# SCH_RETOFISH-V1_2025-09-10.net
KiCad netlist of a schematic drawn in EasyEDA
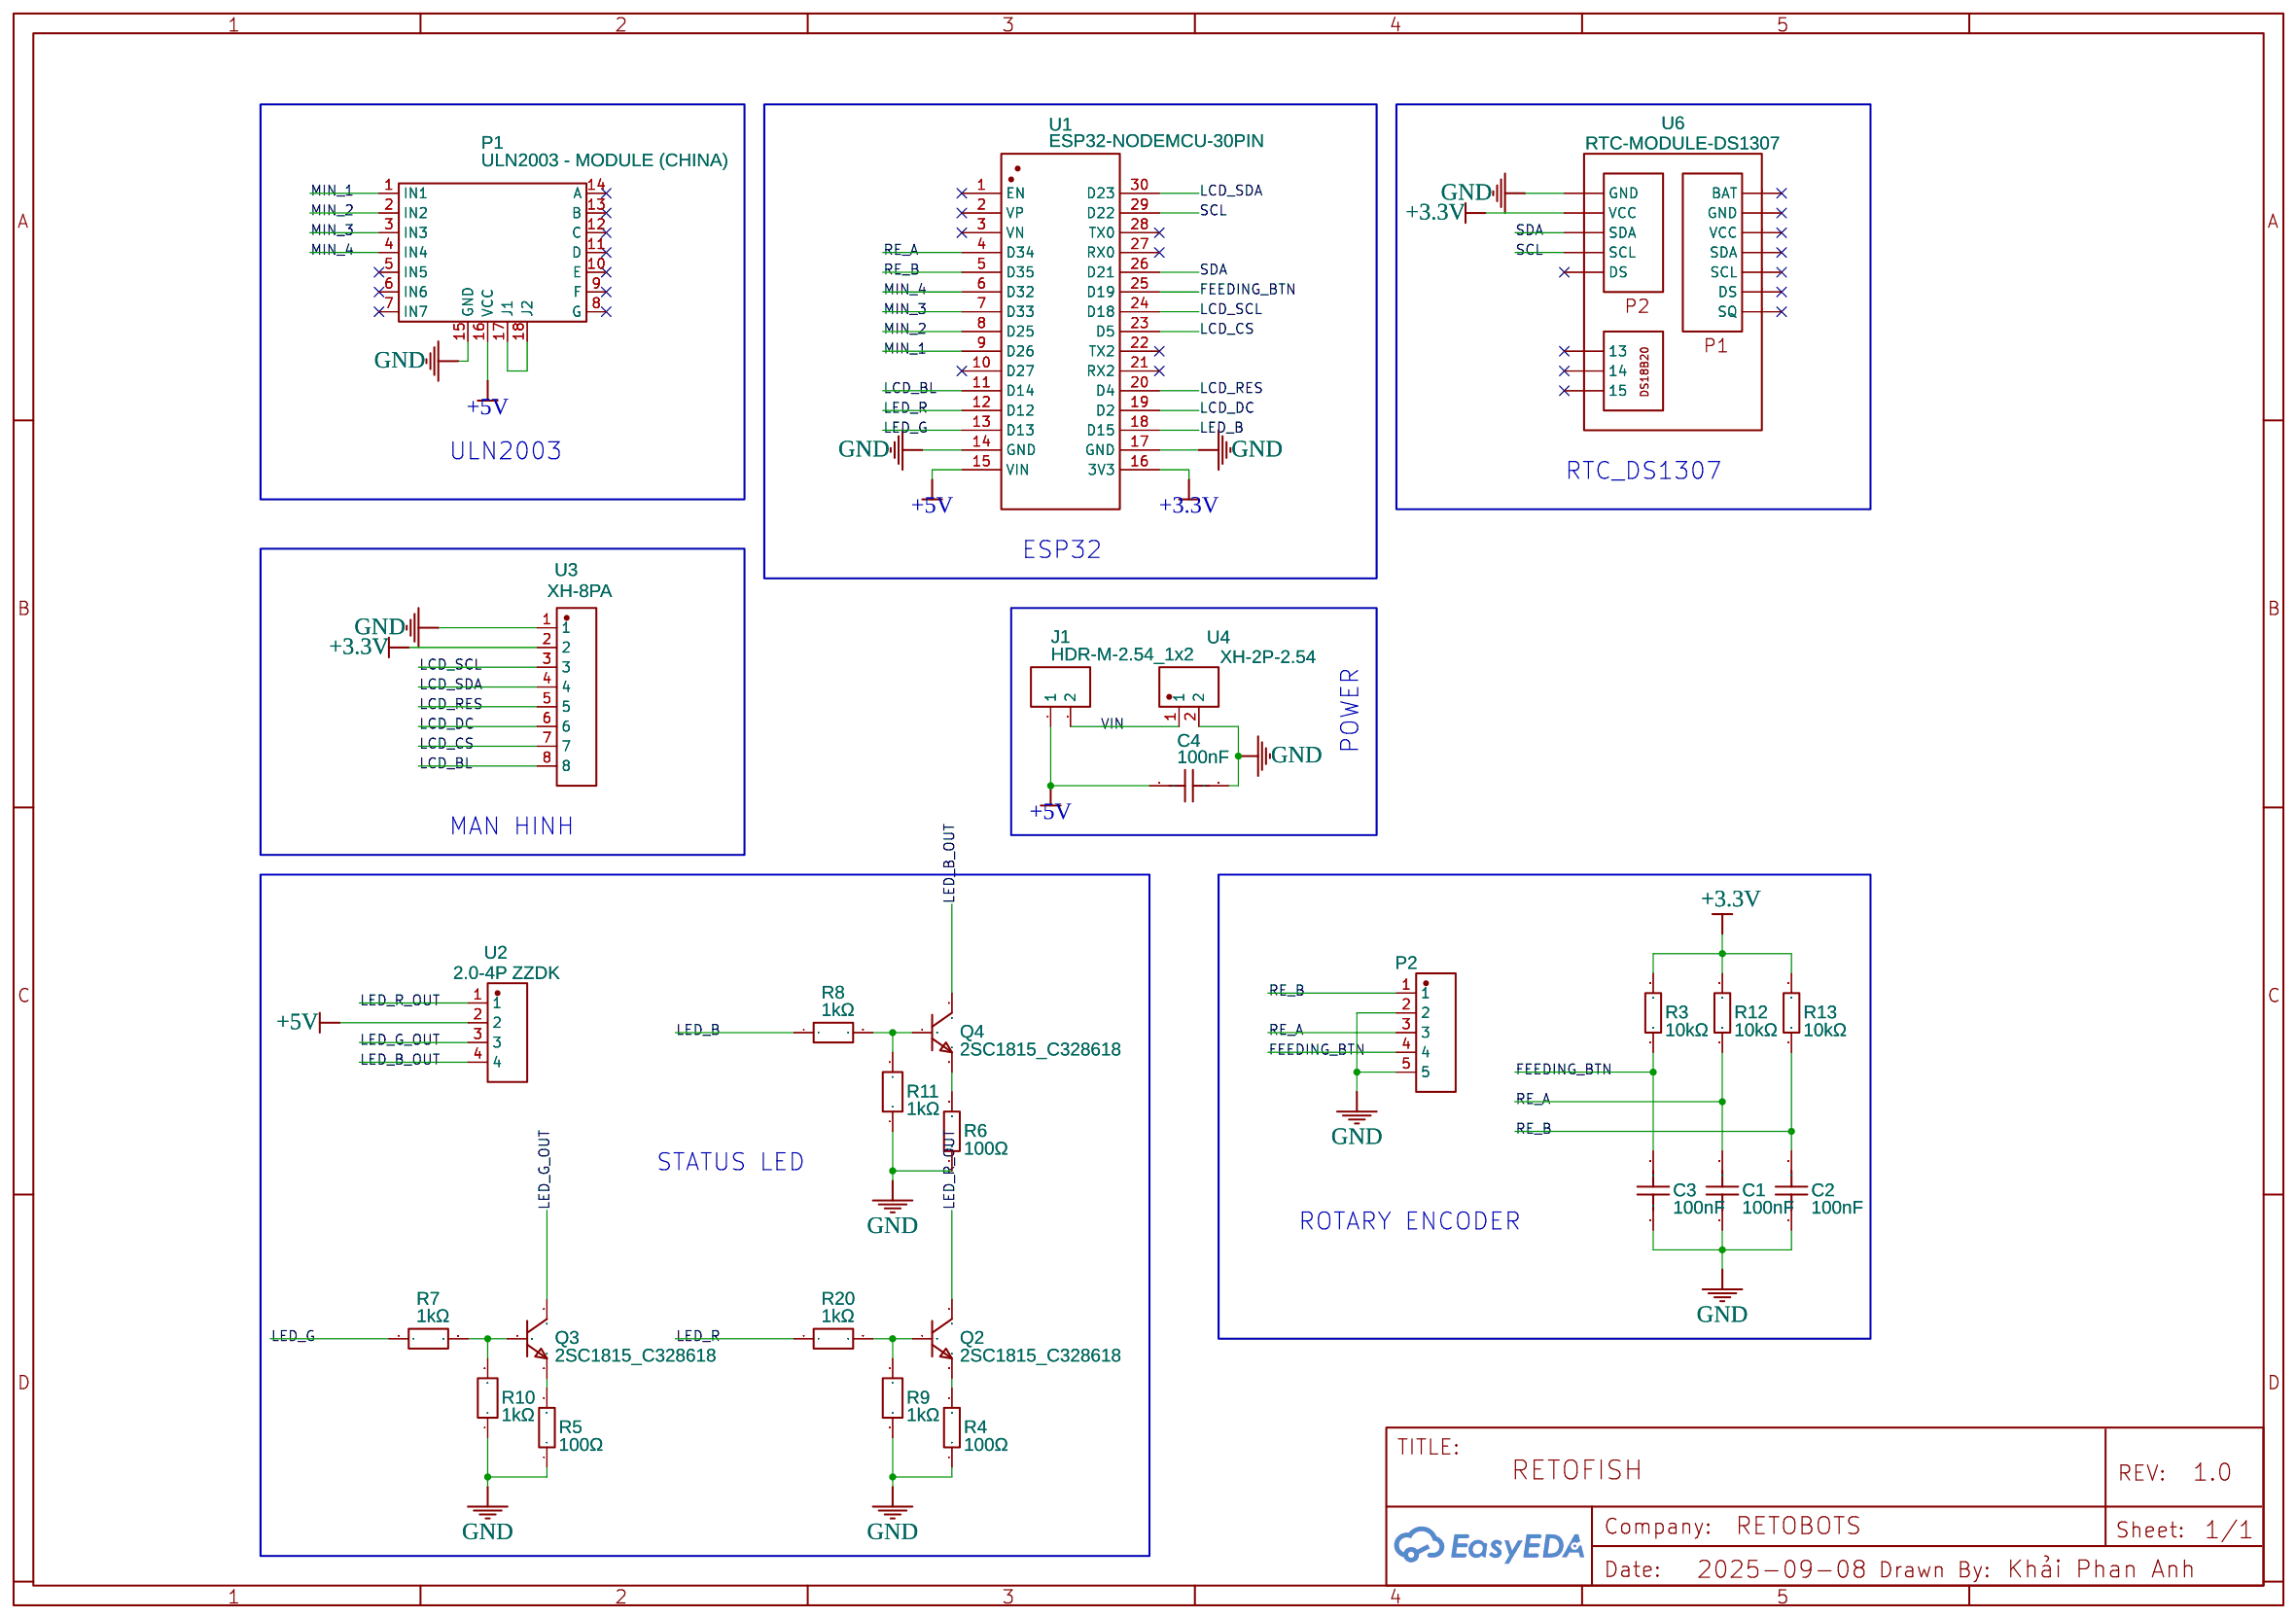
[diagram p0: schematic sheet]

(export (version "E")
  (design (tool "Eeschema 10.0.6"))
  (components
    (comp (ref "C1")
      (value "100nF")
      (fields
        (field (name "Manufacturer Part") "CC1H104ZA1ED3F5P1100")
        (field (name "Manufacturer") "Dersonic(德尔创)")
      )
      (libsource (lib "") (part "CC1H104ZA1ED3F5P1100"))
    )
    (comp (ref "C2")
      (value "100nF")
      (fields
        (field (name "Manufacturer Part") "CC1H104ZA1ED3F5P1100")
        (field (name "Manufacturer") "Dersonic(德尔创)")
      )
      (libsource (lib "") (part "CC1H104ZA1ED3F5P1100"))
    )
    (comp (ref "C3")
      (value "100nF")
      (fields
        (field (name "Manufacturer Part") "CC1H104ZA1ED3F5P1100")
        (field (name "Manufacturer") "Dersonic(德尔创)")
      )
      (libsource (lib "") (part "CC1H104ZA1ED3F5P1100"))
    )
    (comp (ref "C4")
      (value "100nF")
      (fields
        (field (name "Manufacturer Part") "CC1H104ZA1ED3F5P1100")
        (field (name "Manufacturer") "Dersonic(德尔创)")
      )
      (libsource (lib "") (part "CC1H104ZA1ED3F5P1100_1"))
    )
    (comp (ref "J1") (value "HDR-M-2.54_1x2") (libsource (lib "") (part "HDR-M-2.54_1x2")))
    (comp (ref "P1")
      (value "ULN2003 - MODULE (CHINA)")
      (fields
        (field (name "Manufacturer Part") "Female headerHDR1X8-2.54")
        (field (name "Manufacturer") "BOOMELE")
      )
      (libsource (lib "") (part "ULN2003 - MODULE (CHINA)"))
    )
    (comp (ref "P2") (value "XH-2.54-5P") (libsource (lib "") (part "XH-2.54-5P")))
    (comp (ref "Q2")
      (value "2SC1815_C328618")
      (fields (field (name "Manufacturer Part") "2SC1815-GR") (field (name "Manufacturer") "BLUE ROCKET(蓝箭)"))
      (libsource (lib "") (part "2SC1815_C328618"))
    )
    (comp (ref "Q3")
      (value "2SC1815_C328618")
      (fields (field (name "Manufacturer Part") "2SC1815-GR") (field (name "Manufacturer") "BLUE ROCKET(蓝箭)"))
      (libsource (lib "") (part "2SC1815_C328618"))
    )
    (comp (ref "Q4")
      (value "2SC1815_C328618")
      (fields (field (name "Manufacturer Part") "2SC1815-GR") (field (name "Manufacturer") "BLUE ROCKET(蓝箭)"))
      (libsource (lib "") (part "2SC1815_C328618"))
    )
    (comp (ref "R3")
      (value "10kΩ")
      (fields (field (name "Manufacturer Part") "MF1/4W-10KΩ±1% T") (field (name "Manufacturer") "CCO(千志电子)"))
      (libsource (lib "") (part "MF1/4W-10KΩ±1% T52"))
    )
    (comp (ref "R4")
      (value "100Ω")
      (fields (field (name "Manufacturer Part") "CF1/4W-100Ω±5% T") (field (name "Manufacturer") "CCO(千志电子)"))
      (libsource (lib "") (part "CF1/4W-100Ω±5% T52"))
    )
    (comp (ref "R5")
      (value "100Ω")
      (fields (field (name "Manufacturer Part") "CF1/4W-100Ω±5% T") (field (name "Manufacturer") "CCO(千志电子)"))
      (libsource (lib "") (part "CF1/4W-100Ω±5% T52"))
    )
    (comp (ref "R6")
      (value "100Ω")
      (fields (field (name "Manufacturer Part") "CF1/4W-100Ω±5% T") (field (name "Manufacturer") "CCO(千志电子)"))
      (libsource (lib "") (part "CF1/4W-100Ω±5% T52"))
    )
    (comp (ref "R7")
      (value "1kΩ")
      (fields (field (name "Manufacturer Part") "MF1/4W-1KΩ±1%T52") (field (name "Manufacturer") "华星机电"))
      (libsource (lib "") (part "MF1/4W-1KΩ±1%T52_1"))
    )
    (comp (ref "R8")
      (value "1kΩ")
      (fields (field (name "Manufacturer Part") "MF1/4W-1KΩ±1%T52") (field (name "Manufacturer") "华星机电"))
      (libsource (lib "") (part "MF1/4W-1KΩ±1%T52_1"))
    )
    (comp (ref "R9")
      (value "1kΩ")
      (fields (field (name "Manufacturer Part") "MF1/4W-1KΩ±1%T52") (field (name "Manufacturer") "华星机电"))
      (libsource (lib "") (part "MF1/4W-1KΩ±1%T52"))
    )
    (comp (ref "R10")
      (value "1kΩ")
      (fields (field (name "Manufacturer Part") "MF1/4W-1KΩ±1%T52") (field (name "Manufacturer") "华星机电"))
      (libsource (lib "") (part "MF1/4W-1KΩ±1%T52"))
    )
    (comp (ref "R11")
      (value "1kΩ")
      (fields (field (name "Manufacturer Part") "MF1/4W-1KΩ±1%T52") (field (name "Manufacturer") "华星机电"))
      (libsource (lib "") (part "MF1/4W-1KΩ±1%T52"))
    )
    (comp (ref "R12")
      (value "10kΩ")
      (fields (field (name "Manufacturer Part") "MF1/4W-10KΩ±1% T") (field (name "Manufacturer") "CCO(千志电子)"))
      (libsource (lib "") (part "MF1/4W-10KΩ±1% T52"))
    )
    (comp (ref "R13")
      (value "10kΩ")
      (fields (field (name "Manufacturer Part") "MF1/4W-10KΩ±1% T") (field (name "Manufacturer") "CCO(千志电子)"))
      (libsource (lib "") (part "MF1/4W-10KΩ±1% T52"))
    )
    (comp (ref "R20")
      (value "1kΩ")
      (fields (field (name "Manufacturer Part") "MF1/4W-1KΩ±1%T52") (field (name "Manufacturer") "华星机电"))
      (libsource (lib "") (part "MF1/4W-1KΩ±1%T52_1"))
    )
    (comp (ref "U1")
      (value "ESP32-NODEMCU-30PIN")
      (fields (field (name "Manufacturer") "Espreciff"))
      (libsource (lib "") (part "ESP32-NODEMCU-30PIN"))
    )
    (comp (ref "U2")
      (value "2.0-4P ZZDK")
      (fields (field (name "Manufacturer") "SHOU HAN(首韩)"))
      (libsource (lib "") (part "2.0-4P ZZDK"))
    )
    (comp (ref "U3")
      (value "XH-8PA")
      (fields (field (name "Manufacturer") "ZHOURI(洲日)"))
      (libsource (lib "") (part "XH-8PA"))
    )
    (comp (ref "U4") (value "XH-2P-2.54") (libsource (lib "") (part "XH-2P-2.54")))
    (comp (ref "U6") (value "RTC-MODULE-DS1307") (libsource (lib "") (part "SB_RTC-MODULE-DS1307 COPY")))
  )
  (nets
    (net (code "1") (name "+3.3V") (class "Default")
      (node (ref "R12") (pin "2") (pinfunction "2_2") (pintype "unspecified"))
      (node (ref "R13") (pin "2") (pinfunction "2_2") (pintype "unspecified"))
      (node (ref "R3") (pin "2") (pinfunction "2_2") (pintype "unspecified"))
      (node (ref "U1") (pin "16") (pinfunction "3V3_16") (pintype "unspecified"))
      (node (ref "U3") (pin "2") (pinfunction "2_2") (pintype "unspecified"))
      (node (ref "U6") (pin "2") (pinfunction "VCC_2") (pintype "unspecified"))
    )
    (net (code "2") (name "+5V") (class "Default")
      (node (ref "C4") (pin "1") (pinfunction "1_1") (pintype "unspecified"))
      (node (ref "J1") (pin "1") (pinfunction "1_1") (pintype "unspecified"))
      (node (ref "P1") (pin "16") (pinfunction "VCC_16") (pintype "input"))
      (node (ref "U1") (pin "15") (pinfunction "VIN_15") (pintype "unspecified"))
      (node (ref "U2") (pin "2") (pinfunction "2_2") (pintype "unspecified"))
    )
    (net (code "3") (name "/FEEDING_BTN") (class "Default")
      (node (ref "C3") (pin "2") (pinfunction "2_2") (pintype "unspecified"))
      (node (ref "P2") (pin "4") (pinfunction "4_4") (pintype "unspecified"))
      (node (ref "R3") (pin "1") (pinfunction "1_1") (pintype "unspecified"))
      (node (ref "U1") (pin "25") (pinfunction "D19_25") (pintype "unspecified"))
    )
    (net (code "4") (name "/LCD_BL") (class "Default")
      (node (ref "U1") (pin "11") (pinfunction "D14_11") (pintype "unspecified"))
      (node (ref "U3") (pin "8") (pinfunction "8_8") (pintype "unspecified"))
    )
    (net (code "5") (name "/LCD_CS") (class "Default")
      (node (ref "U1") (pin "23") (pinfunction "D5_23") (pintype "unspecified"))
      (node (ref "U3") (pin "7") (pinfunction "7_7") (pintype "unspecified"))
    )
    (net (code "6") (name "/LCD_DC") (class "Default")
      (node (ref "U1") (pin "19") (pinfunction "D2_19") (pintype "unspecified"))
      (node (ref "U3") (pin "6") (pinfunction "6_6") (pintype "unspecified"))
    )
    (net (code "7") (name "/LCD_RES") (class "Default")
      (node (ref "U1") (pin "20") (pinfunction "D4_20") (pintype "unspecified"))
      (node (ref "U3") (pin "5") (pinfunction "5_5") (pintype "unspecified"))
    )
    (net (code "8") (name "/LCD_SCL") (class "Default")
      (node (ref "U1") (pin "24") (pinfunction "D18_24") (pintype "unspecified"))
      (node (ref "U3") (pin "3") (pinfunction "3_3") (pintype "unspecified"))
    )
    (net (code "9") (name "/LCD_SDA") (class "Default")
      (node (ref "U1") (pin "30") (pinfunction "D23_30") (pintype "unspecified"))
      (node (ref "U3") (pin "4") (pinfunction "4_4") (pintype "unspecified"))
    )
    (net (code "10") (name "/LED_B") (class "Default")
      (node (ref "R8") (pin "1") (pinfunction "1_1") (pintype "unspecified"))
      (node (ref "U1") (pin "18") (pinfunction "D15_18") (pintype "unspecified"))
    )
    (net (code "11") (name "/LED_B_OUT") (class "Default")
      (node (ref "Q4") (pin "2") (pinfunction "C_2") (pintype "unspecified"))
      (node (ref "U2") (pin "4") (pinfunction "4_4") (pintype "unspecified"))
    )
    (net (code "12") (name "/LED_G") (class "Default")
      (node (ref "R7") (pin "1") (pinfunction "1_1") (pintype "unspecified"))
      (node (ref "U1") (pin "13") (pinfunction "D13_13") (pintype "unspecified"))
    )
    (net (code "13") (name "/LED_G_OUT") (class "Default")
      (node (ref "Q3") (pin "2") (pinfunction "C_2") (pintype "unspecified"))
      (node (ref "U2") (pin "3") (pinfunction "3_3") (pintype "unspecified"))
    )
    (net (code "14") (name "/LED_R") (class "Default")
      (node (ref "R20") (pin "1") (pinfunction "1_1") (pintype "unspecified"))
      (node (ref "U1") (pin "12") (pinfunction "D12_12") (pintype "unspecified"))
    )
    (net (code "15") (name "/LED_R_OUT") (class "Default")
      (node (ref "Q2") (pin "2") (pinfunction "C_2") (pintype "unspecified"))
      (node (ref "U2") (pin "1") (pinfunction "1_1") (pintype "unspecified"))
    )
    (net (code "16") (name "/MIN_1") (class "Default")
      (node (ref "P1") (pin "1") (pinfunction "IN1_1") (pintype "input"))
      (node (ref "U1") (pin "9") (pinfunction "D26_9") (pintype "unspecified"))
    )
    (net (code "17") (name "/MIN_2") (class "Default")
      (node (ref "P1") (pin "2") (pinfunction "IN2_2") (pintype "input"))
      (node (ref "U1") (pin "8") (pinfunction "D25_8") (pintype "unspecified"))
    )
    (net (code "18") (name "/MIN_3") (class "Default")
      (node (ref "P1") (pin "3") (pinfunction "IN3_3") (pintype "input"))
      (node (ref "U1") (pin "7") (pinfunction "D33_7") (pintype "unspecified"))
    )
    (net (code "19") (name "/MIN_4") (class "Default")
      (node (ref "P1") (pin "4") (pinfunction "IN4_4") (pintype "input"))
      (node (ref "U1") (pin "6") (pinfunction "D32_6") (pintype "unspecified"))
    )
    (net (code "20") (name "/RE_A") (class "Default")
      (node (ref "C1") (pin "2") (pinfunction "2_2") (pintype "unspecified"))
      (node (ref "P2") (pin "3") (pinfunction "3_3") (pintype "unspecified"))
      (node (ref "R12") (pin "1") (pinfunction "1_1") (pintype "unspecified"))
      (node (ref "U1") (pin "4") (pinfunction "D34_4") (pintype "unspecified"))
    )
    (net (code "21") (name "/RE_B") (class "Default")
      (node (ref "C2") (pin "2") (pinfunction "2_2") (pintype "unspecified"))
      (node (ref "P2") (pin "1") (pinfunction "1_1") (pintype "unspecified"))
      (node (ref "R13") (pin "1") (pinfunction "1_1") (pintype "unspecified"))
      (node (ref "U1") (pin "5") (pinfunction "D35_5") (pintype "unspecified"))
    )
    (net (code "22") (name "/SCL") (class "Default")
      (node (ref "U1") (pin "29") (pinfunction "D22_29") (pintype "unspecified"))
      (node (ref "U6") (pin "4") (pinfunction "SCL_4") (pintype "unspecified"))
    )
    (net (code "23") (name "/SDA") (class "Default")
      (node (ref "U1") (pin "26") (pinfunction "D21_26") (pintype "unspecified"))
      (node (ref "U6") (pin "3") (pinfunction "SDA_3") (pintype "unspecified"))
    )
    (net (code "24") (name "/VIN") (class "Default")
      (node (ref "J1") (pin "2") (pinfunction "2_2") (pintype "unspecified"))
      (node (ref "U4") (pin "1") (pinfunction "1_1") (pintype "unspecified"))
    )
    (net (code "25") (name "GND") (class "Default")
      (node (ref "C1") (pin "1") (pinfunction "1_1") (pintype "unspecified"))
      (node (ref "C2") (pin "1") (pinfunction "1_1") (pintype "unspecified"))
      (node (ref "C3") (pin "1") (pinfunction "1_1") (pintype "unspecified"))
      (node (ref "C4") (pin "2") (pinfunction "2_2") (pintype "unspecified"))
      (node (ref "P1") (pin "15") (pinfunction "GND_15") (pintype "input"))
      (node (ref "P2") (pin "2") (pinfunction "2_2") (pintype "unspecified"))
      (node (ref "P2") (pin "5") (pinfunction "5_5") (pintype "unspecified"))
      (node (ref "R10") (pin "1") (pinfunction "1_1") (pintype "unspecified"))
      (node (ref "R11") (pin "1") (pinfunction "1_1") (pintype "unspecified"))
      (node (ref "R4") (pin "1") (pinfunction "1_1") (pintype "unspecified"))
      (node (ref "R5") (pin "1") (pinfunction "1_1") (pintype "unspecified"))
      (node (ref "R6") (pin "1") (pinfunction "1_1") (pintype "unspecified"))
      (node (ref "R9") (pin "1") (pinfunction "1_1") (pintype "unspecified"))
      (node (ref "U1") (pin "14") (pinfunction "GND_14") (pintype "unspecified"))
      (node (ref "U1") (pin "17") (pinfunction "GND_17") (pintype "unspecified"))
      (node (ref "U3") (pin "1") (pinfunction "1_1") (pintype "unspecified"))
      (node (ref "U4") (pin "2") (pinfunction "2_2") (pintype "unspecified"))
      (node (ref "U6") (pin "1") (pinfunction "GND_1") (pintype "unspecified"))
    )
    (net (code "26") (name "Net-(P1-J1)") (class "Default")
      (node (ref "P1") (pin "17") (pinfunction "J1_17") (pintype "input"))
      (node (ref "P1") (pin "18") (pinfunction "J2_18") (pintype "input"))
    )
    (net (code "27") (name "Net-(Q2-B)") (class "Default")
      (node (ref "Q2") (pin "1") (pinfunction "B_1") (pintype "unspecified"))
      (node (ref "R20") (pin "2") (pinfunction "2_2") (pintype "unspecified"))
      (node (ref "R9") (pin "2") (pinfunction "2_2") (pintype "unspecified"))
    )
    (net (code "28") (name "Net-(Q2-E)") (class "Default")
      (node (ref "Q2") (pin "3") (pinfunction "E_3") (pintype "unspecified"))
      (node (ref "R4") (pin "2") (pinfunction "2_2") (pintype "unspecified"))
    )
    (net (code "29") (name "Net-(Q3-B)") (class "Default")
      (node (ref "Q3") (pin "1") (pinfunction "B_1") (pintype "unspecified"))
      (node (ref "R10") (pin "2") (pinfunction "2_2") (pintype "unspecified"))
      (node (ref "R7") (pin "2") (pinfunction "2_2") (pintype "unspecified"))
    )
    (net (code "30") (name "Net-(Q3-E)") (class "Default")
      (node (ref "Q3") (pin "3") (pinfunction "E_3") (pintype "unspecified"))
      (node (ref "R5") (pin "2") (pinfunction "2_2") (pintype "unspecified"))
    )
    (net (code "31") (name "Net-(Q4-B)") (class "Default")
      (node (ref "Q4") (pin "1") (pinfunction "B_1") (pintype "unspecified"))
      (node (ref "R11") (pin "2") (pinfunction "2_2") (pintype "unspecified"))
      (node (ref "R8") (pin "2") (pinfunction "2_2") (pintype "unspecified"))
    )
    (net (code "32") (name "Net-(Q4-E)") (class "Default")
      (node (ref "Q4") (pin "3") (pinfunction "E_3") (pintype "unspecified"))
      (node (ref "R6") (pin "2") (pinfunction "2_2") (pintype "unspecified"))
    )
    (net (code "33") (name "unconnected-(P1-A-Pad14)") (class "Default")
      (node (ref "P1") (pin "14") (pinfunction "A_14") (pintype "input+no_connect"))
    )
    (net (code "34") (name "unconnected-(P1-B-Pad13)") (class "Default")
      (node (ref "P1") (pin "13") (pinfunction "B_13") (pintype "input+no_connect"))
    )
    (net (code "35") (name "unconnected-(P1-C-Pad12)") (class "Default")
      (node (ref "P1") (pin "12") (pinfunction "C_12") (pintype "input+no_connect"))
    )
    (net (code "36") (name "unconnected-(P1-D-Pad11)") (class "Default")
      (node (ref "P1") (pin "11") (pinfunction "D_11") (pintype "input+no_connect"))
    )
    (net (code "37") (name "unconnected-(P1-E-Pad10)") (class "Default")
      (node (ref "P1") (pin "10") (pinfunction "E_10") (pintype "input+no_connect"))
    )
    (net (code "38") (name "unconnected-(P1-F-Pad9)") (class "Default")
      (node (ref "P1") (pin "9") (pinfunction "F_9") (pintype "input+no_connect"))
    )
    (net (code "39") (name "unconnected-(P1-G-Pad8)") (class "Default")
      (node (ref "P1") (pin "8") (pinfunction "G_8") (pintype "input+no_connect"))
    )
    (net (code "40") (name "unconnected-(P1-IN5-Pad5)") (class "Default")
      (node (ref "P1") (pin "5") (pinfunction "IN5_5") (pintype "input+no_connect"))
    )
    (net (code "41") (name "unconnected-(P1-IN6-Pad6)") (class "Default")
      (node (ref "P1") (pin "6") (pinfunction "IN6_6") (pintype "input+no_connect"))
    )
    (net (code "42") (name "unconnected-(P1-IN7-Pad7)") (class "Default")
      (node (ref "P1") (pin "7") (pinfunction "IN7_7") (pintype "input+no_connect"))
    )
    (net (code "43") (name "unconnected-(U1-D27-Pad10)") (class "Default")
      (node (ref "U1") (pin "10") (pinfunction "D27_10") (pintype "unspecified+no_connect"))
    )
    (net (code "44") (name "unconnected-(U1-EN-Pad1)") (class "Default")
      (node (ref "U1") (pin "1") (pinfunction "EN_1") (pintype "unspecified+no_connect"))
    )
    (net (code "45") (name "unconnected-(U1-RX0-Pad27)") (class "Default")
      (node (ref "U1") (pin "27") (pinfunction "RX0_27") (pintype "unspecified+no_connect"))
    )
    (net (code "46") (name "unconnected-(U1-RX2-Pad21)") (class "Default")
      (node (ref "U1") (pin "21") (pinfunction "RX2_21") (pintype "unspecified+no_connect"))
    )
    (net (code "47") (name "unconnected-(U1-TX0-Pad28)") (class "Default")
      (node (ref "U1") (pin "28") (pinfunction "TX0_28") (pintype "unspecified+no_connect"))
    )
    (net (code "48") (name "unconnected-(U1-TX2-Pad22)") (class "Default")
      (node (ref "U1") (pin "22") (pinfunction "TX2_22") (pintype "unspecified+no_connect"))
    )
    (net (code "49") (name "unconnected-(U1-VN-Pad3)") (class "Default")
      (node (ref "U1") (pin "3") (pinfunction "VN_3") (pintype "unspecified+no_connect"))
    )
    (net (code "50") (name "unconnected-(U1-VP-Pad2)") (class "Default")
      (node (ref "U1") (pin "2") (pinfunction "VP_2") (pintype "unspecified+no_connect"))
    )
    (net (code "51") (name "unconnected-(U6-BAT-Pad6)") (class "Default")
      (node (ref "U6") (pin "6") (pinfunction "BAT_6") (pintype "unspecified+no_connect"))
    )
    (net (code "52") (name "unconnected-(U6-DS-Pad5)") (class "Default")
      (node (ref "U6") (pin "5") (pinfunction "DS_5") (pintype "unspecified+no_connect"))
    )
    (net (code "53") (name "unconnected-(U6-DS-Pad11)") (class "Default")
      (node (ref "U6") (pin "11") (pinfunction "DS_11") (pintype "unspecified+no_connect"))
    )
    (net (code "54") (name "unconnected-(U6-GND-Pad7)") (class "Default")
      (node (ref "U6") (pin "7") (pinfunction "GND_7") (pintype "unspecified+no_connect"))
    )
    (net (code "55") (name "unconnected-(U6-Pad13)") (class "Default")
      (node (ref "U6") (pin "13") (pinfunction "13_13") (pintype "unspecified+no_connect"))
    )
    (net (code "56") (name "unconnected-(U6-Pad14)") (class "Default")
      (node (ref "U6") (pin "14") (pinfunction "14_14") (pintype "unspecified+no_connect"))
    )
    (net (code "57") (name "unconnected-(U6-Pad15)") (class "Default")
      (node (ref "U6") (pin "15") (pinfunction "15_15") (pintype "unspecified+no_connect"))
    )
    (net (code "58") (name "unconnected-(U6-SCL-Pad10)") (class "Default")
      (node (ref "U6") (pin "10") (pinfunction "SCL_10") (pintype "unspecified+no_connect"))
    )
    (net (code "59") (name "unconnected-(U6-SDA-Pad9)") (class "Default")
      (node (ref "U6") (pin "9") (pinfunction "SDA_9") (pintype "unspecified+no_connect"))
    )
    (net (code "60") (name "unconnected-(U6-SQ-Pad12)") (class "Default")
      (node (ref "U6") (pin "12") (pinfunction "SQ_12") (pintype "unspecified+no_connect"))
    )
    (net (code "61") (name "unconnected-(U6-VCC-Pad8)") (class "Default")
      (node (ref "U6") (pin "8") (pinfunction "VCC_8") (pintype "unspecified+no_connect"))
    )
  )
)
